# printcore_connector.net
KiCad netlist of a schematic drawn in EAGLE
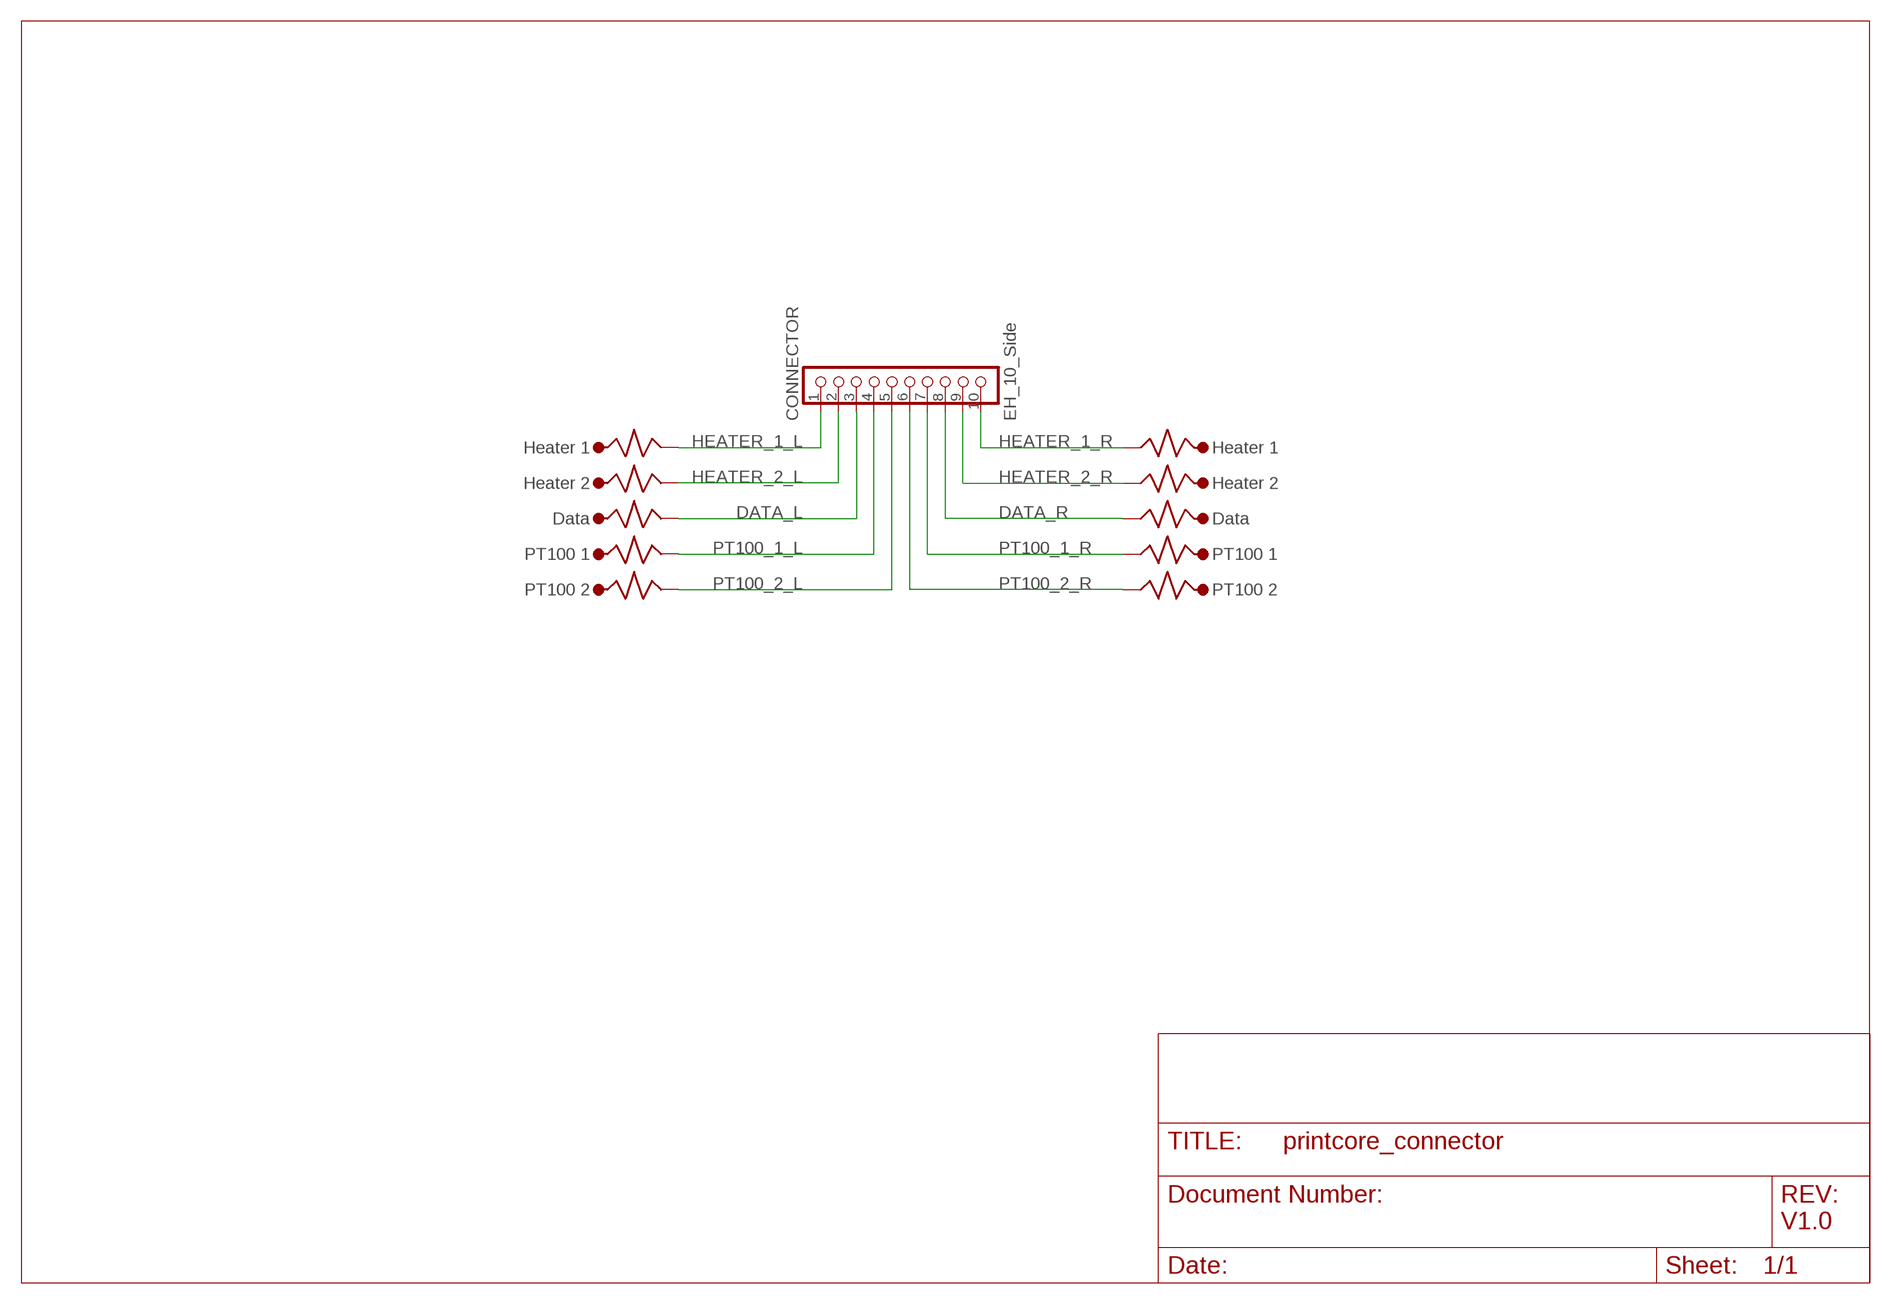
[diagram p0: schematic, sheet 1]

(export (version "E")
  (design (tool "Eeschema 10.0.6"))
  (components
    (comp (ref "CONNECTOR")
      (value "EH_10_Side")
      (footprint "eagle-import:S10B-EH")
      (libsource (lib "eagle-import") (part "EH_S10B-EH"))
    )
    (comp (ref "U$1")
      (value "ULTIMAKER_PRINTCORE_CONNNECTOR")
      (footprint "eagle-import:ULTIMAKER_PRINTCORE_CONNECTOR")
      (libsource (lib "eagle-import") (part "ULTIMAKER_PRINTCORE_CONNNECTOR"))
    )
    (comp (ref "U$3")
      (value "ULTIMAKER_PRINTCORE_CONNNECTOR")
      (footprint "eagle-import:ULTIMAKER_PRINTCORE_CONNECTOR")
      (libsource (lib "eagle-import") (part "ULTIMAKER_PRINTCORE_CONNNECTOR"))
    )
  )
  (nets
    (net (code "1") (name "/DATA_L") (class "Default")
      (node (ref "CONNECTOR") (pin "3") (pinfunction "3_3") (pintype "passive"))
      (node (ref "U$1") (pin "DATA") (pinfunction "DATA_DATA") (pintype "bidirectional"))
    )
    (net (code "2") (name "/DATA_R") (class "Default")
      (node (ref "CONNECTOR") (pin "8") (pinfunction "8_8") (pintype "passive"))
      (node (ref "U$3") (pin "DATA") (pinfunction "DATA_DATA") (pintype "bidirectional"))
    )
    (net (code "3") (name "/HEATER_1_L") (class "Default")
      (node (ref "CONNECTOR") (pin "1") (pinfunction "1_1") (pintype "passive"))
      (node (ref "U$1") (pin "HEATER@1") (pinfunction "HEATER_HEATER@1") (pintype "bidirectional"))
    )
    (net (code "4") (name "/HEATER_1_R") (class "Default")
      (node (ref "CONNECTOR") (pin "10") (pinfunction "10_10") (pintype "passive"))
      (node (ref "U$3") (pin "HEATER@1") (pinfunction "HEATER_HEATER@1") (pintype "bidirectional"))
    )
    (net (code "5") (name "/HEATER_2_L") (class "Default")
      (node (ref "CONNECTOR") (pin "2") (pinfunction "2_2") (pintype "passive"))
      (node (ref "U$1") (pin "HEATER@2") (pinfunction "HEATER_HEATER@2") (pintype "bidirectional"))
    )
    (net (code "6") (name "/HEATER_2_R") (class "Default")
      (node (ref "CONNECTOR") (pin "9") (pinfunction "9_9") (pintype "passive"))
      (node (ref "U$3") (pin "HEATER@2") (pinfunction "HEATER_HEATER@2") (pintype "bidirectional"))
    )
    (net (code "7") (name "/PT100_1_L") (class "Default")
      (node (ref "CONNECTOR") (pin "4") (pinfunction "4_4") (pintype "passive"))
      (node (ref "U$1") (pin "PT100@1") (pinfunction "PT100_PT100@1") (pintype "bidirectional"))
    )
    (net (code "8") (name "/PT100_1_R") (class "Default")
      (node (ref "CONNECTOR") (pin "7") (pinfunction "7_7") (pintype "passive"))
      (node (ref "U$3") (pin "PT100@1") (pinfunction "PT100_PT100@1") (pintype "bidirectional"))
    )
    (net (code "9") (name "/PT100_2_L") (class "Default")
      (node (ref "CONNECTOR") (pin "5") (pinfunction "5_5") (pintype "passive"))
      (node (ref "U$1") (pin "PT100@2") (pinfunction "PT100_PT100@2") (pintype "bidirectional"))
    )
    (net (code "10") (name "/PT100_2_R") (class "Default")
      (node (ref "CONNECTOR") (pin "6") (pinfunction "6_6") (pintype "passive"))
      (node (ref "U$3") (pin "PT100@2") (pinfunction "PT100_PT100@2") (pintype "bidirectional"))
    )
  )
)
